# DC_Link.net
KiCad netlist of a schematic drawn in Altium Designer
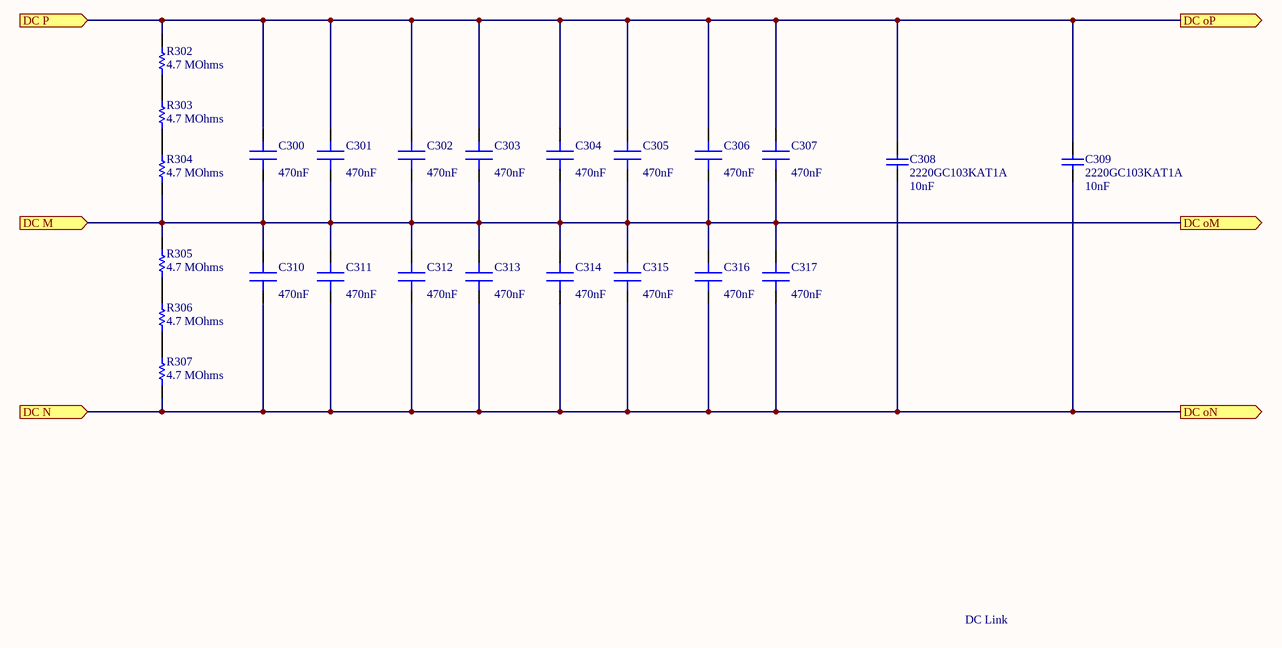
[diagram p0: DC_Link.SchDoc]

(export (version "E")
  (design (tool "Eeschema 10.0.6"))
  (components
    (comp (ref "C300")
      (value "CKG45NX7T2J474M500JH")
      (footprint "C_1812_CKG45NX7T2J474M500JH")
      (fields
        (field (name "MANUFACTURER") "TDK")
        (field (name "CAPACITANCE") "470nF")
        (field (name "TOLERANCE") "20%")
      )
      (libsource (lib "Altium_Library_POWERLAB") (part "CKG45NX7T2J474M500JH"))
    )
    (comp (ref "C301")
      (value "CKG45NX7T2J474M500JH")
      (footprint "C_1812_CKG45NX7T2J474M500JH")
      (fields
        (field (name "MANUFACTURER") "TDK")
        (field (name "CAPACITANCE") "470nF")
        (field (name "TOLERANCE") "20%")
      )
      (libsource (lib "Altium_Library_POWERLAB") (part "CKG45NX7T2J474M500JH"))
    )
    (comp (ref "C302")
      (value "CKG45NX7T2J474M500JH")
      (footprint "C_1812_CKG45NX7T2J474M500JH")
      (fields
        (field (name "MANUFACTURER") "TDK")
        (field (name "CAPACITANCE") "470nF")
        (field (name "TOLERANCE") "20%")
      )
      (libsource (lib "Altium_Library_POWERLAB") (part "CKG45NX7T2J474M500JH"))
    )
    (comp (ref "C303")
      (value "CKG45NX7T2J474M500JH")
      (footprint "C_1812_CKG45NX7T2J474M500JH")
      (fields
        (field (name "MANUFACTURER") "TDK")
        (field (name "CAPACITANCE") "470nF")
        (field (name "TOLERANCE") "20%")
      )
      (libsource (lib "Altium_Library_POWERLAB") (part "CKG45NX7T2J474M500JH"))
    )
    (comp (ref "C304")
      (value "CKG45NX7T2J474M500JH")
      (footprint "C_1812_CKG45NX7T2J474M500JH")
      (fields
        (field (name "MANUFACTURER") "TDK")
        (field (name "CAPACITANCE") "470nF")
        (field (name "TOLERANCE") "20%")
      )
      (libsource (lib "Altium_Library_POWERLAB") (part "CKG45NX7T2J474M500JH"))
    )
    (comp (ref "C305")
      (value "CKG45NX7T2J474M500JH")
      (footprint "C_1812_CKG45NX7T2J474M500JH")
      (fields
        (field (name "MANUFACTURER") "TDK")
        (field (name "CAPACITANCE") "470nF")
        (field (name "TOLERANCE") "20%")
      )
      (libsource (lib "Altium_Library_POWERLAB") (part "CKG45NX7T2J474M500JH"))
    )
    (comp (ref "C306")
      (value "CKG45NX7T2J474M500JH")
      (footprint "C_1812_CKG45NX7T2J474M500JH")
      (fields
        (field (name "MANUFACTURER") "TDK")
        (field (name "CAPACITANCE") "470nF")
        (field (name "TOLERANCE") "20%")
      )
      (libsource (lib "Altium_Library_POWERLAB") (part "CKG45NX7T2J474M500JH"))
    )
    (comp (ref "C307")
      (value "CKG45NX7T2J474M500JH")
      (footprint "C_1812_CKG45NX7T2J474M500JH")
      (fields
        (field (name "MANUFACTURER") "TDK")
        (field (name "CAPACITANCE") "470nF")
        (field (name "TOLERANCE") "20%")
      )
      (libsource (lib "Altium_Library_POWERLAB") (part "CKG45NX7T2J474M500JH"))
    )
    (comp (ref "C308")
      (value "2220GC103KAT1A")
      (footprint "CAPC5750X330X64LL40T39")
      (fields (field (name "CAPACITANCE") "10nF") (field (name "MANUFACTURER") "AVX"))
      (libsource (lib "Altium Content Vault") (part "CAP-NP-2"))
    )
    (comp (ref "C309")
      (value "2220GC103KAT1A")
      (footprint "CAPC5750X330X64LL40T39")
      (fields (field (name "CAPACITANCE") "10nF") (field (name "MANUFACTURER") "AVX"))
      (libsource (lib "Altium Content Vault") (part "CAP-NP-2"))
    )
    (comp (ref "C310")
      (value "CKG45NX7T2J474M500JH")
      (footprint "C_1812_CKG45NX7T2J474M500JH")
      (fields
        (field (name "MANUFACTURER") "TDK")
        (field (name "CAPACITANCE") "470nF")
        (field (name "TOLERANCE") "20%")
      )
      (libsource (lib "Altium_Library_POWERLAB") (part "CKG45NX7T2J474M500JH"))
    )
    (comp (ref "C311")
      (value "CKG45NX7T2J474M500JH")
      (footprint "C_1812_CKG45NX7T2J474M500JH")
      (fields
        (field (name "MANUFACTURER") "TDK")
        (field (name "CAPACITANCE") "470nF")
        (field (name "TOLERANCE") "20%")
      )
      (libsource (lib "Altium_Library_POWERLAB") (part "CKG45NX7T2J474M500JH"))
    )
    (comp (ref "C312")
      (value "CKG45NX7T2J474M500JH")
      (footprint "C_1812_CKG45NX7T2J474M500JH")
      (fields
        (field (name "MANUFACTURER") "TDK")
        (field (name "CAPACITANCE") "470nF")
        (field (name "TOLERANCE") "20%")
      )
      (libsource (lib "Altium_Library_POWERLAB") (part "CKG45NX7T2J474M500JH"))
    )
    (comp (ref "C313")
      (value "CKG45NX7T2J474M500JH")
      (footprint "C_1812_CKG45NX7T2J474M500JH")
      (fields
        (field (name "MANUFACTURER") "TDK")
        (field (name "CAPACITANCE") "470nF")
        (field (name "TOLERANCE") "20%")
      )
      (libsource (lib "Altium_Library_POWERLAB") (part "CKG45NX7T2J474M500JH"))
    )
    (comp (ref "C314")
      (value "CKG45NX7T2J474M500JH")
      (footprint "C_1812_CKG45NX7T2J474M500JH")
      (fields
        (field (name "MANUFACTURER") "TDK")
        (field (name "CAPACITANCE") "470nF")
        (field (name "TOLERANCE") "20%")
      )
      (libsource (lib "Altium_Library_POWERLAB") (part "CKG45NX7T2J474M500JH"))
    )
    (comp (ref "C315")
      (value "CKG45NX7T2J474M500JH")
      (footprint "C_1812_CKG45NX7T2J474M500JH")
      (fields
        (field (name "MANUFACTURER") "TDK")
        (field (name "CAPACITANCE") "470nF")
        (field (name "TOLERANCE") "20%")
      )
      (libsource (lib "Altium_Library_POWERLAB") (part "CKG45NX7T2J474M500JH"))
    )
    (comp (ref "C316")
      (value "CKG45NX7T2J474M500JH")
      (footprint "C_1812_CKG45NX7T2J474M500JH")
      (fields
        (field (name "MANUFACTURER") "TDK")
        (field (name "CAPACITANCE") "470nF")
        (field (name "TOLERANCE") "20%")
      )
      (libsource (lib "Altium_Library_POWERLAB") (part "CKG45NX7T2J474M500JH"))
    )
    (comp (ref "C317")
      (value "CKG45NX7T2J474M500JH")
      (footprint "C_1812_CKG45NX7T2J474M500JH")
      (fields
        (field (name "MANUFACTURER") "TDK")
        (field (name "CAPACITANCE") "470nF")
        (field (name "TOLERANCE") "20%")
      )
      (libsource (lib "Altium_Library_POWERLAB") (part "CKG45NX7T2J474M500JH"))
    )
    (comp (ref "R302")
      (value "4.7 MOhms")
      (footprint "RESC3216X60X45LL10T20")
      (fields (field (name "MANUFACTURER") "Vishay Dale") (field (name "PART NUMBER") "CRCW12064M70FKEA"))
      (libsource (lib "Altium Content Vault") (part "RES"))
    )
    (comp (ref "R303")
      (value "4.7 MOhms")
      (footprint "RESC3216X60X45LL10T20")
      (fields (field (name "MANUFACTURER") "Vishay Dale") (field (name "PART NUMBER") "CRCW12064M70FKEA"))
      (libsource (lib "Altium Content Vault") (part "RES"))
    )
    (comp (ref "R304")
      (value "4.7 MOhms")
      (footprint "RESC3216X60X45LL10T20")
      (fields (field (name "MANUFACTURER") "Vishay Dale") (field (name "PART NUMBER") "CRCW12064M70FKEA"))
      (libsource (lib "Altium Content Vault") (part "RES"))
    )
    (comp (ref "R305")
      (value "4.7 MOhms")
      (footprint "RESC3216X60X45LL10T20")
      (fields (field (name "MANUFACTURER") "Vishay Dale") (field (name "PART NUMBER") "CRCW12064M70FKEA"))
      (libsource (lib "Altium Content Vault") (part "RES"))
    )
    (comp (ref "R306")
      (value "4.7 MOhms")
      (footprint "RESC3216X60X45LL10T20")
      (fields (field (name "MANUFACTURER") "Vishay Dale") (field (name "PART NUMBER") "CRCW12064M70FKEA"))
      (libsource (lib "Altium Content Vault") (part "RES"))
    )
    (comp (ref "R307")
      (value "4.7 MOhms")
      (footprint "RESC3216X60X45LL10T20")
      (fields (field (name "MANUFACTURER") "Vishay Dale") (field (name "PART NUMBER") "CRCW12064M70FKEA"))
      (libsource (lib "Altium Content Vault") (part "RES"))
    )
  )
  (nets
    (net (code "1") (name "/DC M") (class "Default")
      (node (ref "C300") (pin "1") (pinfunction "1_1") (pintype "passive"))
      (node (ref "C301") (pin "1") (pinfunction "1_1") (pintype "passive"))
      (node (ref "C302") (pin "1") (pinfunction "1_1") (pintype "passive"))
      (node (ref "C303") (pin "1") (pinfunction "1_1") (pintype "passive"))
      (node (ref "C304") (pin "1") (pinfunction "1_1") (pintype "passive"))
      (node (ref "C305") (pin "1") (pinfunction "1_1") (pintype "passive"))
      (node (ref "C306") (pin "1") (pinfunction "1_1") (pintype "passive"))
      (node (ref "C307") (pin "1") (pinfunction "1_1") (pintype "passive"))
      (node (ref "C310") (pin "2") (pinfunction "2_2") (pintype "passive"))
      (node (ref "C311") (pin "2") (pinfunction "2_2") (pintype "passive"))
      (node (ref "C312") (pin "2") (pinfunction "2_2") (pintype "passive"))
      (node (ref "C313") (pin "2") (pinfunction "2_2") (pintype "passive"))
      (node (ref "C314") (pin "2") (pinfunction "2_2") (pintype "passive"))
      (node (ref "C315") (pin "2") (pinfunction "2_2") (pintype "passive"))
      (node (ref "C316") (pin "2") (pinfunction "2_2") (pintype "passive"))
      (node (ref "C317") (pin "2") (pinfunction "2_2") (pintype "passive"))
      (node (ref "R304") (pin "2") (pinfunction "2_2") (pintype "passive"))
      (node (ref "R305") (pin "1") (pinfunction "1_1") (pintype "passive"))
    )
    (net (code "2") (name "/DC N") (class "Default")
      (node (ref "C308") (pin "1") (pinfunction "1_1") (pintype "passive"))
      (node (ref "C309") (pin "1") (pinfunction "1_1") (pintype "passive"))
      (node (ref "C310") (pin "1") (pinfunction "1_1") (pintype "passive"))
      (node (ref "C311") (pin "1") (pinfunction "1_1") (pintype "passive"))
      (node (ref "C312") (pin "1") (pinfunction "1_1") (pintype "passive"))
      (node (ref "C313") (pin "1") (pinfunction "1_1") (pintype "passive"))
      (node (ref "C314") (pin "1") (pinfunction "1_1") (pintype "passive"))
      (node (ref "C315") (pin "1") (pinfunction "1_1") (pintype "passive"))
      (node (ref "C316") (pin "1") (pinfunction "1_1") (pintype "passive"))
      (node (ref "C317") (pin "1") (pinfunction "1_1") (pintype "passive"))
      (node (ref "R307") (pin "2") (pinfunction "2_2") (pintype "passive"))
    )
    (net (code "3") (name "/DC P") (class "Default")
      (node (ref "C300") (pin "2") (pinfunction "2_2") (pintype "passive"))
      (node (ref "C301") (pin "2") (pinfunction "2_2") (pintype "passive"))
      (node (ref "C302") (pin "2") (pinfunction "2_2") (pintype "passive"))
      (node (ref "C303") (pin "2") (pinfunction "2_2") (pintype "passive"))
      (node (ref "C304") (pin "2") (pinfunction "2_2") (pintype "passive"))
      (node (ref "C305") (pin "2") (pinfunction "2_2") (pintype "passive"))
      (node (ref "C306") (pin "2") (pinfunction "2_2") (pintype "passive"))
      (node (ref "C307") (pin "2") (pinfunction "2_2") (pintype "passive"))
      (node (ref "C308") (pin "2") (pinfunction "2_2") (pintype "passive"))
      (node (ref "C309") (pin "2") (pinfunction "2_2") (pintype "passive"))
      (node (ref "R302") (pin "1") (pinfunction "1_1") (pintype "passive"))
    )
    (net (code "4") (name "Net-(R302-Pad2)") (class "Default")
      (node (ref "R302") (pin "2") (pinfunction "2_2") (pintype "passive"))
      (node (ref "R303") (pin "1") (pinfunction "1_1") (pintype "passive"))
    )
    (net (code "5") (name "Net-(R303-Pad2)") (class "Default")
      (node (ref "R303") (pin "2") (pinfunction "2_2") (pintype "passive"))
      (node (ref "R304") (pin "1") (pinfunction "1_1") (pintype "passive"))
    )
    (net (code "6") (name "Net-(R305-Pad2)") (class "Default")
      (node (ref "R305") (pin "2") (pinfunction "2_2") (pintype "passive"))
      (node (ref "R306") (pin "1") (pinfunction "1_1") (pintype "passive"))
    )
    (net (code "7") (name "Net-(R306-Pad2)") (class "Default")
      (node (ref "R306") (pin "2") (pinfunction "2_2") (pintype "passive"))
      (node (ref "R307") (pin "1") (pinfunction "1_1") (pintype "passive"))
    )
  )
)
